# gismov.net
KiCad netlist of a schematic drawn in EAGLE
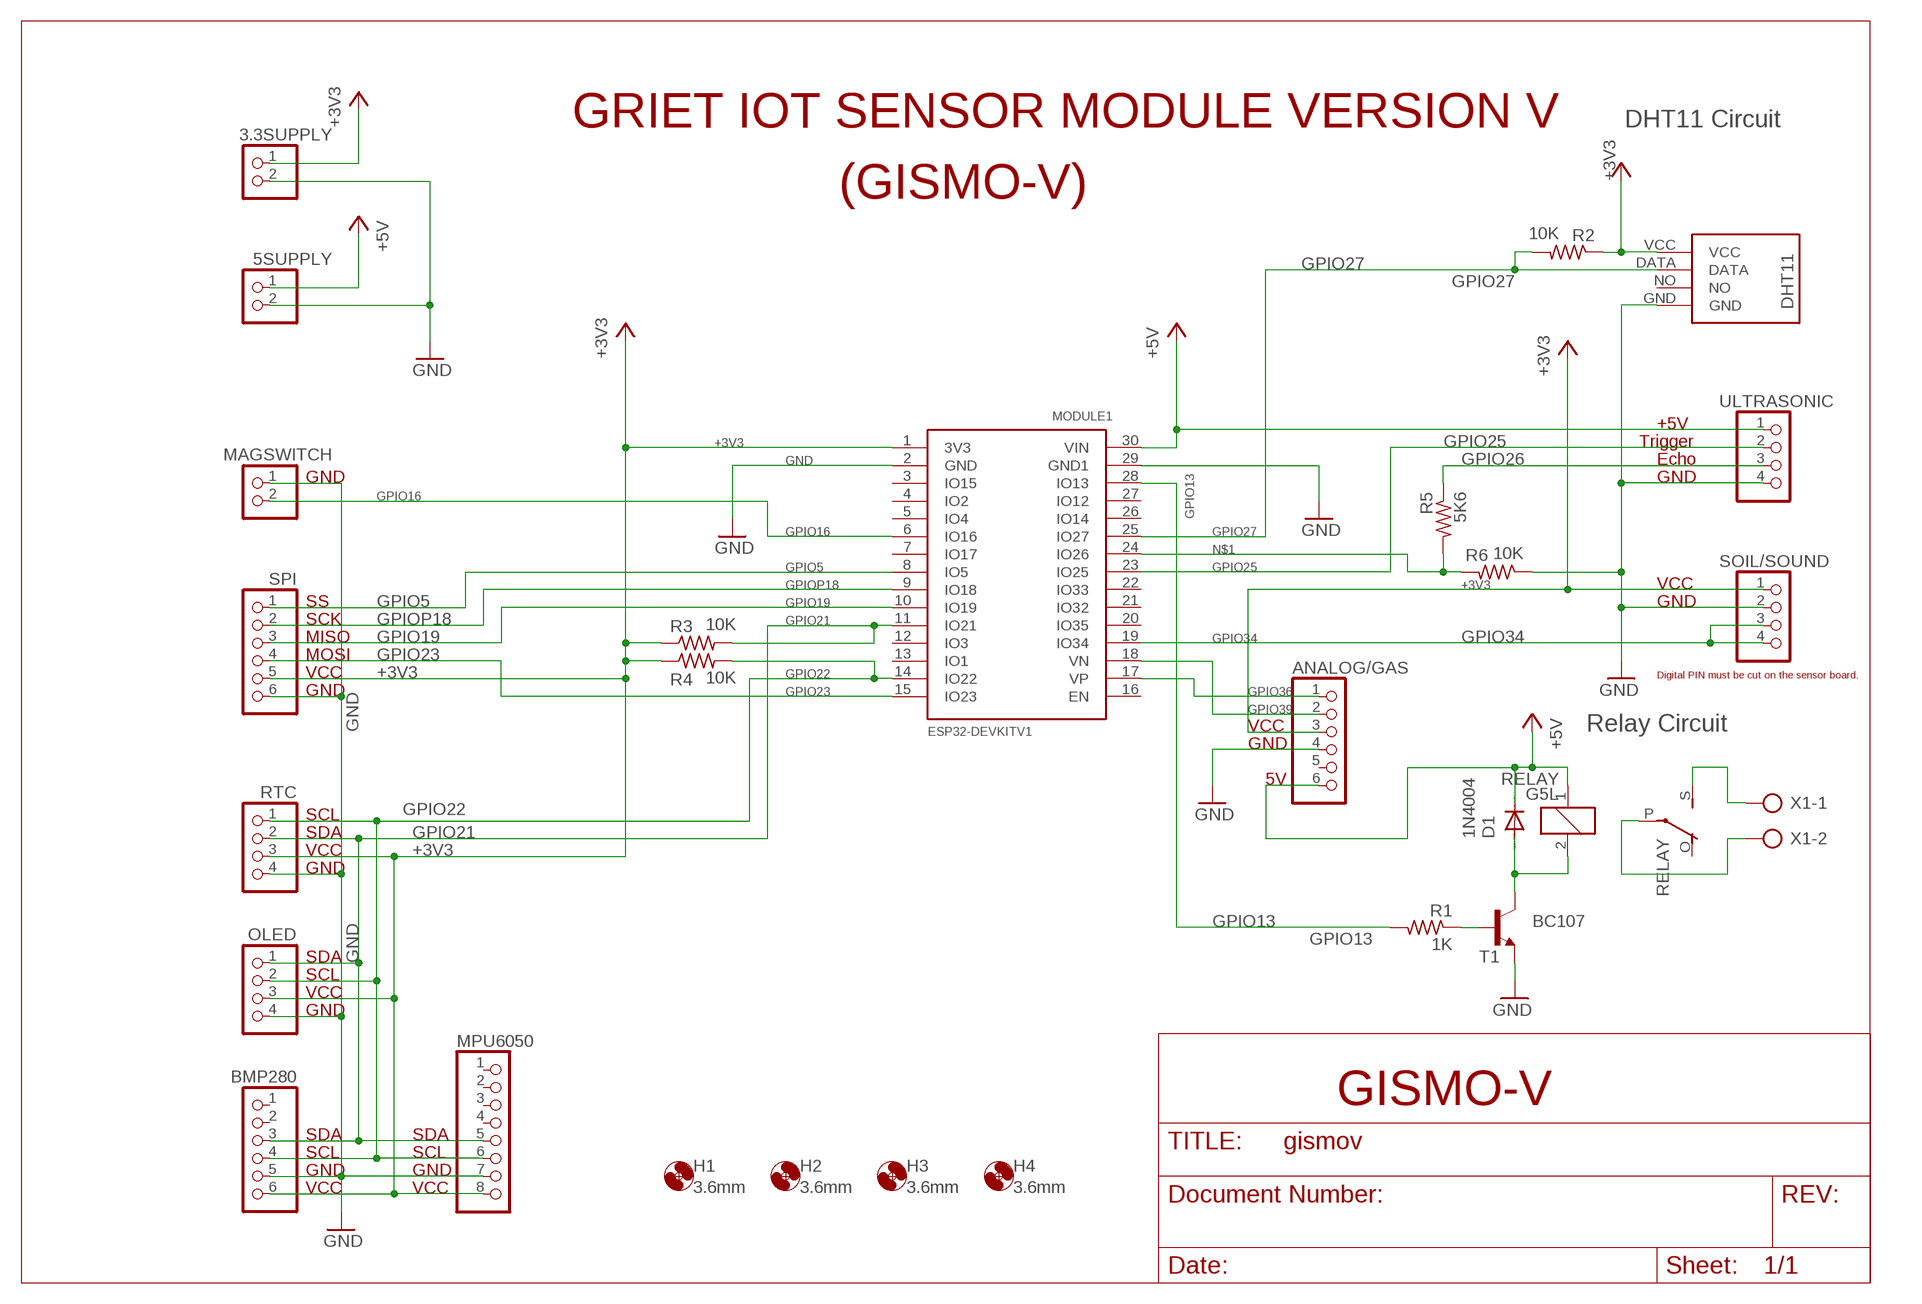
[diagram p0: schematic, sheet 1]

(export (version "E")
  (design (tool "Eeschema 10.0.6"))
  (components
    (comp (ref "3.3SUPPLY")
      (value "PINHD-1X2")
      (footprint "eagle-import:1X02")
      (libsource (lib "eagle-import") (part "PINHD-1X2"))
    )
    (comp (ref "5SUPPLY")
      (value "PINHD-1X2")
      (footprint "eagle-import:1X02")
      (libsource (lib "eagle-import") (part "PINHD-1X2"))
    )
    (comp (ref "ANALOG/GAS")
      (value "PINHD-1X6")
      (footprint "eagle-import:1X06")
      (libsource (lib "eagle-import") (part "PINHD-1X6"))
    )
    (comp (ref "BMP280")
      (value "PINHD-1X6")
      (footprint "eagle-import:1X06")
      (libsource (lib "eagle-import") (part "PINHD-1X6"))
    )
    (comp (ref "D1")
      (value "1N4004")
      (footprint "eagle-import:DO41-10")
      (libsource (lib "eagle-import") (part "1N4004"))
    )
    (comp (ref "H1")
      (value "3.6mm")
      (footprint "eagle-import:3,6")
      (libsource (lib "eagle-import") (part "MOUNT-HOLE3.6"))
    )
    (comp (ref "H2")
      (value "3.6mm")
      (footprint "eagle-import:3,6")
      (libsource (lib "eagle-import") (part "MOUNT-HOLE3.6"))
    )
    (comp (ref "H3")
      (value "3.6mm")
      (footprint "eagle-import:3,6")
      (libsource (lib "eagle-import") (part "MOUNT-HOLE3.6"))
    )
    (comp (ref "H4")
      (value "3.6mm")
      (footprint "eagle-import:3,6")
      (libsource (lib "eagle-import") (part "MOUNT-HOLE3.6"))
    )
    (comp (ref "MAGSWITCH")
      (value "PINHD-1X2")
      (footprint "eagle-import:1X02")
      (libsource (lib "eagle-import") (part "PINHD-1X2"))
    )
    (comp (ref "MODULE1")
      (value "ESP32DEVKITV1")
      (footprint "eagle-import:ESP32-DEVKITV1")
      (libsource (lib "eagle-import") (part "ESP32DEVKITV1"))
    )
    (comp (ref "MPU6050")
      (value "PINHD-1X8")
      (footprint "eagle-import:1X08")
      (libsource (lib "eagle-import") (part "PINHD-1X8"))
    )
    (comp (ref "OLED")
      (value "PINHD-1X4")
      (footprint "eagle-import:1X04")
      (libsource (lib "eagle-import") (part "PINHD-1X4"))
    )
    (comp (ref "R1")
      (value "1K")
      (footprint "eagle-import:0204_7")
      (libsource (lib "eagle-import") (part "R-US_0204/7"))
    )
    (comp (ref "R2")
      (value "10K")
      (footprint "eagle-import:0204_7")
      (libsource (lib "eagle-import") (part "R-US_0204/7"))
    )
    (comp (ref "R3")
      (value "10K")
      (footprint "eagle-import:0204_7")
      (libsource (lib "eagle-import") (part "R-US_0204/7"))
    )
    (comp (ref "R4")
      (value "10K")
      (footprint "eagle-import:0204_7")
      (libsource (lib "eagle-import") (part "R-US_0204/7"))
    )
    (comp (ref "R5")
      (value "5K6")
      (footprint "eagle-import:0204_7")
      (libsource (lib "eagle-import") (part "R-US_0204/7"))
    )
    (comp (ref "R6")
      (value "10K")
      (footprint "eagle-import:0204_7")
      (libsource (lib "eagle-import") (part "R-US_0204/7"))
    )
    (comp (ref "RELAY")
      (value "G5L")
      (footprint "eagle-import:G5LE")
      (libsource (lib "eagle-import") (part "G5L"))
    )
    (comp (ref "RTC")
      (value "PINHD-1X4")
      (footprint "eagle-import:1X04")
      (libsource (lib "eagle-import") (part "PINHD-1X4"))
    )
    (comp (ref "SOIL/SOUND")
      (value "PINHD-1X4")
      (footprint "eagle-import:1X04")
      (libsource (lib "eagle-import") (part "PINHD-1X4"))
    )
    (comp (ref "SPI")
      (value "PINHD-1X6")
      (footprint "eagle-import:1X06")
      (libsource (lib "eagle-import") (part "PINHD-1X6"))
    )
    (comp (ref "T1")
      (value "BC107")
      (footprint "eagle-import:TO18")
      (libsource (lib "eagle-import") (part "-NPN-TO18-EBCBC107A"))
    )
    (comp (ref "U$2")
      (value "DHT11")
      (footprint "eagle-import:DHT11")
      (libsource (lib "eagle-import") (part "DHT11"))
    )
    (comp (ref "ULTRASONIC")
      (value "PINHD-1X4")
      (footprint "eagle-import:1X04")
      (libsource (lib "eagle-import") (part "PINHD-1X4"))
    )
    (comp (ref "X1")
      (value "AK500/2")
      (footprint "eagle-import:AK500_2")
      (libsource (lib "eagle-import") (part "AK500/2"))
    )
  )
  (nets
    (net (code "1") (name "+3V3") (class "Default")
      (node (ref "3.3SUPPLY") (pin "1") (pinfunction "1_1") (pintype "passive"))
      (node (ref "ANALOG/GAS") (pin "3") (pinfunction "3_3") (pintype "passive"))
      (node (ref "BMP280") (pin "6") (pinfunction "6_6") (pintype "passive"))
      (node (ref "MODULE1") (pin "1") (pinfunction "3V3_1") (pintype "bidirectional"))
      (node (ref "MPU6050") (pin "8") (pinfunction "8_8") (pintype "passive"))
      (node (ref "OLED") (pin "3") (pinfunction "3_3") (pintype "passive"))
      (node (ref "R2") (pin "1") (pinfunction "1_1") (pintype "passive"))
      (node (ref "R3") (pin "1") (pinfunction "1_1") (pintype "passive"))
      (node (ref "R4") (pin "1") (pinfunction "1_1") (pintype "passive"))
      (node (ref "RTC") (pin "3") (pinfunction "3_3") (pintype "passive"))
      (node (ref "SOIL/SOUND") (pin "1") (pinfunction "1_1") (pintype "passive"))
      (node (ref "SPI") (pin "5") (pinfunction "5_5") (pintype "passive"))
      (node (ref "U$2") (pin "VCC") (pinfunction "VCC_VCC") (pintype "bidirectional"))
    )
    (net (code "2") (name "+5V") (class "Default")
      (node (ref "5SUPPLY") (pin "1") (pinfunction "1_1") (pintype "passive"))
      (node (ref "ANALOG/GAS") (pin "6") (pinfunction "6_6") (pintype "passive"))
      (node (ref "D1") (pin "C") (pinfunction "C_C") (pintype "passive"))
      (node (ref "MODULE1") (pin "30") (pinfunction "VIN_30") (pintype "bidirectional"))
      (node (ref "RELAY") (pin "1") (pinfunction "1_1") (pintype "passive"))
      (node (ref "ULTRASONIC") (pin "1") (pinfunction "1_1") (pintype "passive"))
    )
    (net (code "3") (name "/GPIO5") (class "Default")
      (node (ref "MODULE1") (pin "8") (pinfunction "IO5_8") (pintype "bidirectional"))
      (node (ref "SPI") (pin "1") (pinfunction "1_1") (pintype "passive"))
    )
    (net (code "4") (name "/GPIO13") (class "Default")
      (node (ref "MODULE1") (pin "28") (pinfunction "IO13_28") (pintype "bidirectional"))
      (node (ref "R1") (pin "2") (pinfunction "2_2") (pintype "passive"))
    )
    (net (code "5") (name "/GPIO16") (class "Default")
      (node (ref "MAGSWITCH") (pin "2") (pinfunction "2_2") (pintype "passive"))
      (node (ref "MODULE1") (pin "6") (pinfunction "IO16_6") (pintype "bidirectional"))
    )
    (net (code "6") (name "/GPIO19") (class "Default")
      (node (ref "MODULE1") (pin "10") (pinfunction "IO19_10") (pintype "bidirectional"))
      (node (ref "SPI") (pin "3") (pinfunction "3_3") (pintype "passive"))
    )
    (net (code "7") (name "/GPIO21") (class "Default")
      (node (ref "BMP280") (pin "3") (pinfunction "3_3") (pintype "passive"))
      (node (ref "MODULE1") (pin "11") (pinfunction "IO21_11") (pintype "bidirectional"))
      (node (ref "MPU6050") (pin "5") (pinfunction "5_5") (pintype "passive"))
      (node (ref "OLED") (pin "1") (pinfunction "1_1") (pintype "passive"))
      (node (ref "R3") (pin "2") (pinfunction "2_2") (pintype "passive"))
      (node (ref "RTC") (pin "2") (pinfunction "2_2") (pintype "passive"))
    )
    (net (code "8") (name "/GPIO22") (class "Default")
      (node (ref "BMP280") (pin "4") (pinfunction "4_4") (pintype "passive"))
      (node (ref "MODULE1") (pin "14") (pinfunction "IO22_14") (pintype "bidirectional"))
      (node (ref "MPU6050") (pin "6") (pinfunction "6_6") (pintype "passive"))
      (node (ref "OLED") (pin "2") (pinfunction "2_2") (pintype "passive"))
      (node (ref "R4") (pin "2") (pinfunction "2_2") (pintype "passive"))
      (node (ref "RTC") (pin "1") (pinfunction "1_1") (pintype "passive"))
    )
    (net (code "9") (name "/GPIO23") (class "Default")
      (node (ref "MODULE1") (pin "15") (pinfunction "IO23_15") (pintype "bidirectional"))
      (node (ref "SPI") (pin "4") (pinfunction "4_4") (pintype "passive"))
    )
    (net (code "10") (name "/GPIO25") (class "Default")
      (node (ref "MODULE1") (pin "23") (pinfunction "IO25_23") (pintype "bidirectional"))
      (node (ref "ULTRASONIC") (pin "2") (pinfunction "2_2") (pintype "passive"))
    )
    (net (code "11") (name "/GPIO26") (class "Default")
      (node (ref "R5") (pin "1") (pinfunction "1_1") (pintype "passive"))
      (node (ref "ULTRASONIC") (pin "3") (pinfunction "3_3") (pintype "passive"))
    )
    (net (code "12") (name "/GPIO27") (class "Default")
      (node (ref "MODULE1") (pin "25") (pinfunction "IO27_25") (pintype "bidirectional"))
      (node (ref "R2") (pin "2") (pinfunction "2_2") (pintype "passive"))
      (node (ref "U$2") (pin "DATA") (pinfunction "DATA_DATA") (pintype "bidirectional"))
    )
    (net (code "13") (name "/GPIO34") (class "Default")
      (node (ref "MODULE1") (pin "19") (pinfunction "IO34_19") (pintype "bidirectional"))
      (node (ref "SOIL/SOUND") (pin "3") (pinfunction "3_3") (pintype "passive"))
      (node (ref "SOIL/SOUND") (pin "4") (pinfunction "4_4") (pintype "passive"))
    )
    (net (code "14") (name "/GPIO36") (class "Default")
      (node (ref "ANALOG/GAS") (pin "1") (pinfunction "1_1") (pintype "passive"))
      (node (ref "MODULE1") (pin "17") (pinfunction "VP_17") (pintype "bidirectional"))
    )
    (net (code "15") (name "/GPIO39") (class "Default")
      (node (ref "ANALOG/GAS") (pin "2") (pinfunction "2_2") (pintype "passive"))
      (node (ref "MODULE1") (pin "18") (pinfunction "VN_18") (pintype "bidirectional"))
    )
    (net (code "16") (name "/GPIOP18") (class "Default")
      (node (ref "MODULE1") (pin "9") (pinfunction "IO18_9") (pintype "bidirectional"))
      (node (ref "SPI") (pin "2") (pinfunction "2_2") (pintype "passive"))
    )
    (net (code "17") (name "/N$1") (class "Default")
      (node (ref "MODULE1") (pin "24") (pinfunction "IO26_24") (pintype "bidirectional"))
      (node (ref "R5") (pin "2") (pinfunction "2_2") (pintype "passive"))
      (node (ref "R6") (pin "2") (pinfunction "2_2") (pintype "passive"))
    )
    (net (code "18") (name "GND") (class "Default")
      (node (ref "3.3SUPPLY") (pin "2") (pinfunction "2_2") (pintype "passive"))
      (node (ref "5SUPPLY") (pin "2") (pinfunction "2_2") (pintype "passive"))
      (node (ref "ANALOG/GAS") (pin "4") (pinfunction "4_4") (pintype "passive"))
      (node (ref "BMP280") (pin "5") (pinfunction "5_5") (pintype "passive"))
      (node (ref "MAGSWITCH") (pin "1") (pinfunction "1_1") (pintype "passive"))
      (node (ref "MODULE1") (pin "2") (pinfunction "GND_2") (pintype "bidirectional"))
      (node (ref "MODULE1") (pin "29") (pinfunction "GND1_29") (pintype "bidirectional"))
      (node (ref "MPU6050") (pin "7") (pinfunction "7_7") (pintype "passive"))
      (node (ref "OLED") (pin "4") (pinfunction "4_4") (pintype "passive"))
      (node (ref "R6") (pin "1") (pinfunction "1_1") (pintype "passive"))
      (node (ref "RTC") (pin "4") (pinfunction "4_4") (pintype "passive"))
      (node (ref "SOIL/SOUND") (pin "2") (pinfunction "2_2") (pintype "passive"))
      (node (ref "SPI") (pin "6") (pinfunction "6_6") (pintype "passive"))
      (node (ref "T1") (pin "1") (pinfunction "E_1") (pintype "passive"))
      (node (ref "U$2") (pin "GND") (pinfunction "GND_GND") (pintype "bidirectional"))
      (node (ref "ULTRASONIC") (pin "4") (pinfunction "4_4") (pintype "passive"))
    )
    (net (code "19") (name "Net-(T1-B)") (class "Default")
      (node (ref "R1") (pin "1") (pinfunction "1_1") (pintype "passive"))
      (node (ref "T1") (pin "2") (pinfunction "B_2") (pintype "passive"))
    )
    (net (code "20") (name "Net-(T1-C)") (class "Default")
      (node (ref "D1") (pin "A") (pinfunction "A_A") (pintype "passive"))
      (node (ref "RELAY") (pin "2") (pinfunction "2_2") (pintype "passive"))
      (node (ref "T1") (pin "3") (pinfunction "C_3") (pintype "passive"))
    )
    (net (code "21") (name "Net-(X1A-KL)") (class "Default")
      (node (ref "RELAY") (pin "S") (pinfunction "S_S") (pintype "passive"))
      (node (ref "X1") (pin "1") (pinfunction "KL_1") (pintype "passive"))
    )
    (net (code "22") (name "Net-(X1B-KL)") (class "Default")
      (node (ref "RELAY") (pin "P") (pinfunction "P_P") (pintype "passive"))
      (node (ref "X1") (pin "2") (pinfunction "KL_2") (pintype "passive"))
    )
    (net (code "23") (name "unconnected-(ANALOG/GAS-Pad5)") (class "Default")
      (node (ref "ANALOG/GAS") (pin "5") (pinfunction "5_5") (pintype "passive"))
    )
    (net (code "24") (name "unconnected-(BMP280-Pad1)") (class "Default")
      (node (ref "BMP280") (pin "1") (pinfunction "1_1") (pintype "passive"))
    )
    (net (code "25") (name "unconnected-(BMP280-Pad2)") (class "Default")
      (node (ref "BMP280") (pin "2") (pinfunction "2_2") (pintype "passive"))
    )
    (net (code "26") (name "unconnected-(MODULE1-EN-Pad16)") (class "Default")
      (node (ref "MODULE1") (pin "16") (pinfunction "EN_16") (pintype "bidirectional"))
    )
    (net (code "27") (name "unconnected-(MODULE1-IO1-Pad13)") (class "Default")
      (node (ref "MODULE1") (pin "13") (pinfunction "IO1_13") (pintype "bidirectional"))
    )
    (net (code "28") (name "unconnected-(MODULE1-IO2-Pad4)") (class "Default")
      (node (ref "MODULE1") (pin "4") (pinfunction "IO2_4") (pintype "bidirectional"))
    )
    (net (code "29") (name "unconnected-(MODULE1-IO3-Pad12)") (class "Default")
      (node (ref "MODULE1") (pin "12") (pinfunction "IO3_12") (pintype "bidirectional"))
    )
    (net (code "30") (name "unconnected-(MODULE1-IO4-Pad5)") (class "Default")
      (node (ref "MODULE1") (pin "5") (pinfunction "IO4_5") (pintype "bidirectional"))
    )
    (net (code "31") (name "unconnected-(MODULE1-IO12-Pad27)") (class "Default")
      (node (ref "MODULE1") (pin "27") (pinfunction "IO12_27") (pintype "bidirectional"))
    )
    (net (code "32") (name "unconnected-(MODULE1-IO14-Pad26)") (class "Default")
      (node (ref "MODULE1") (pin "26") (pinfunction "IO14_26") (pintype "bidirectional"))
    )
    (net (code "33") (name "unconnected-(MODULE1-IO15-Pad3)") (class "Default")
      (node (ref "MODULE1") (pin "3") (pinfunction "IO15_3") (pintype "bidirectional"))
    )
    (net (code "34") (name "unconnected-(MODULE1-IO17-Pad7)") (class "Default")
      (node (ref "MODULE1") (pin "7") (pinfunction "IO17_7") (pintype "bidirectional"))
    )
    (net (code "35") (name "unconnected-(MODULE1-IO32-Pad21)") (class "Default")
      (node (ref "MODULE1") (pin "21") (pinfunction "IO32_21") (pintype "bidirectional"))
    )
    (net (code "36") (name "unconnected-(MODULE1-IO33-Pad22)") (class "Default")
      (node (ref "MODULE1") (pin "22") (pinfunction "IO33_22") (pintype "bidirectional"))
    )
    (net (code "37") (name "unconnected-(MODULE1-IO35-Pad20)") (class "Default")
      (node (ref "MODULE1") (pin "20") (pinfunction "IO35_20") (pintype "bidirectional"))
    )
    (net (code "38") (name "unconnected-(MPU6050-Pad1)") (class "Default")
      (node (ref "MPU6050") (pin "1") (pinfunction "1_1") (pintype "passive"))
    )
    (net (code "39") (name "unconnected-(MPU6050-Pad2)") (class "Default")
      (node (ref "MPU6050") (pin "2") (pinfunction "2_2") (pintype "passive"))
    )
    (net (code "40") (name "unconnected-(MPU6050-Pad3)") (class "Default")
      (node (ref "MPU6050") (pin "3") (pinfunction "3_3") (pintype "passive"))
    )
    (net (code "41") (name "unconnected-(MPU6050-Pad4)") (class "Default")
      (node (ref "MPU6050") (pin "4") (pinfunction "4_4") (pintype "passive"))
    )
    (net (code "42") (name "unconnected-(RELAY-PadO)") (class "Default")
      (node (ref "RELAY") (pin "O") (pinfunction "O_O") (pintype "passive"))
    )
    (net (code "43") (name "unconnected-(U$2-PadNO)") (class "Default")
      (node (ref "U$2") (pin "NO") (pinfunction "NO_NO") (pintype "bidirectional"))
    )
  )
)
